# Scheme.net
KiCad netlist of a schematic drawn in Altium Designer
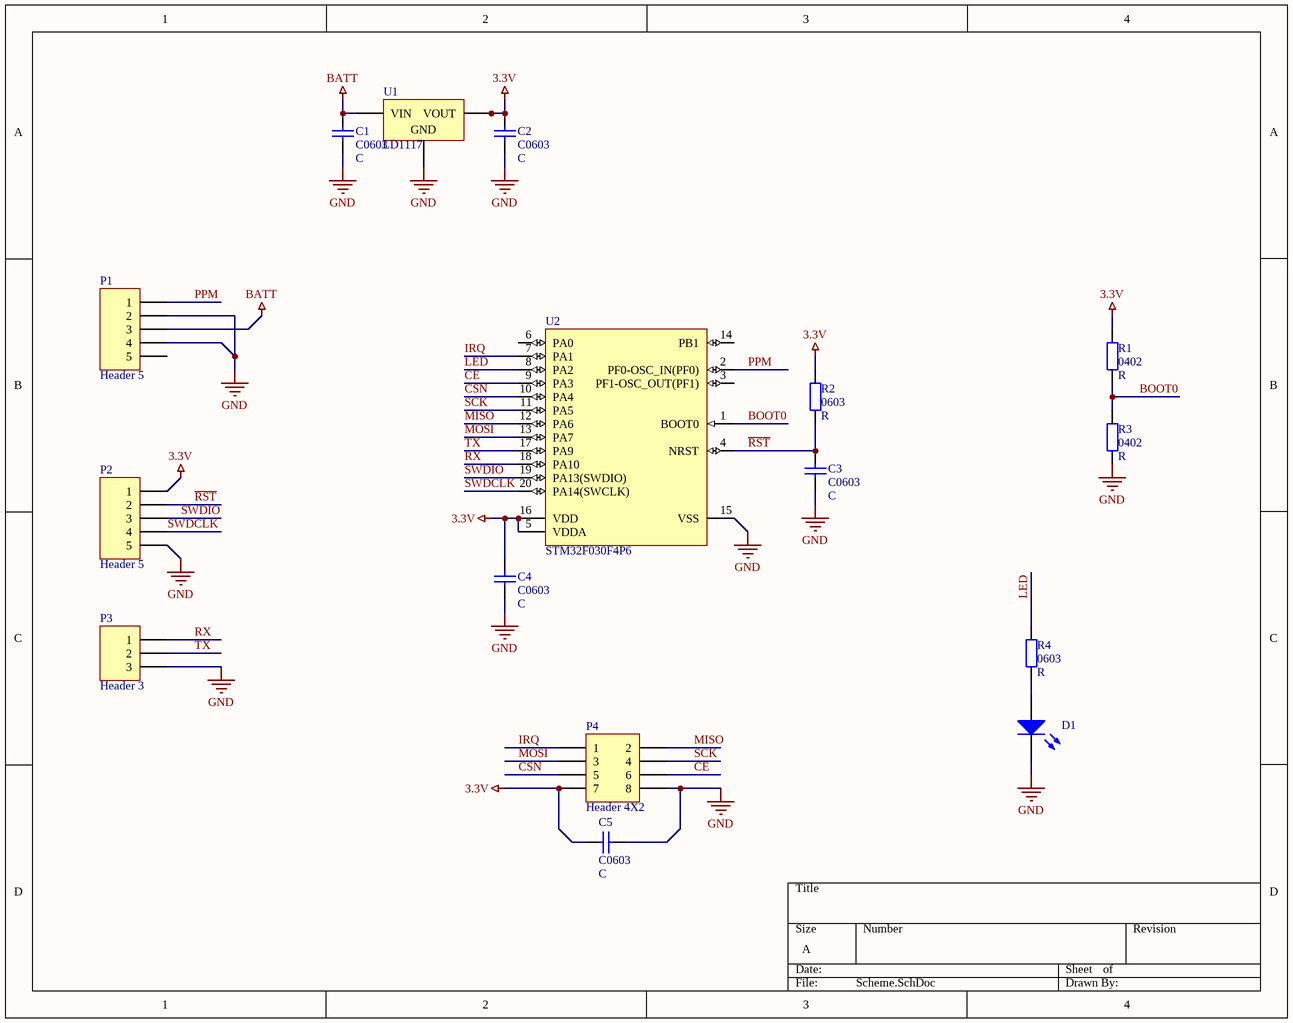
[diagram p0: Scheme.SchDoc]

(export (version "E")
  (design (tool "Eeschema 10.0.6"))
  (components
    (comp (ref "C1")
      (value "C")
      (footprint "C0603")
      (description "Generic capacitor")
      (libsource (lib "_RLC") (part "Cap"))
    )
    (comp (ref "C2")
      (value "C")
      (footprint "C0603")
      (description "Generic capacitor")
      (libsource (lib "_RLC") (part "Cap"))
    )
    (comp (ref "C3")
      (value "C")
      (footprint "C0603")
      (description "Generic capacitor")
      (libsource (lib "_RLC") (part "Cap"))
    )
    (comp (ref "C4")
      (value "C")
      (footprint "C0603")
      (description "Generic capacitor")
      (libsource (lib "_RLC") (part "Cap"))
    )
    (comp (ref "C5")
      (value "C")
      (footprint "C0603")
      (description "Generic capacitor")
      (libsource (lib "_RLC") (part "Cap"))
    )
    (comp (ref "D1")
      (value "LEDX")
      (footprint "LED 0805 RED")
      (description "Typical LED")
      (libsource (lib "_Diodes") (part "LEDX"))
    )
    (comp (ref "P1")
      (value "Header 5")
      (footprint "HEADER 1X5 FEMALE")
      (description "Header, 5-Pin")
      (fields (field (name "PUBLISHER") "Altium Limited"))
      (libsource (lib "_Connectors") (part "Header 5"))
    )
    (comp (ref "P2")
      (value "Header 5")
      (footprint "HEADER 1X5 FEMALE")
      (description "Header, 5-Pin")
      (fields (field (name "PUBLISHER") "Altium Limited"))
      (libsource (lib "_Connectors") (part "Header 5"))
    )
    (comp (ref "P3")
      (value "Header 3")
      (footprint "HEADER 1X3 MALE")
      (description "Header, 3-Pin")
      (fields (field (name "PUBLISHER") "Altium Limited"))
      (libsource (lib "_Connectors") (part "Header 3"))
    )
    (comp (ref "P4")
      (value "Header 4X2")
      (footprint "HEADER 2X4 FEMALE")
      (description "Header, 4-Pin, Dual row")
      (fields (field (name "PUBLISHER") "Altium Limited"))
      (libsource (lib "_Connectors") (part "Header 4X2"))
    )
    (comp (ref "R1")
      (value "R")
      (footprint "0402")
      (description "Generic resistor")
      (libsource (lib "_RLC") (part "Res"))
    )
    (comp (ref "R2")
      (value "R")
      (footprint "0603")
      (description "Generic resistor")
      (libsource (lib "_RLC") (part "Res"))
    )
    (comp (ref "R3")
      (value "R")
      (footprint "0402")
      (description "Generic resistor")
      (libsource (lib "_RLC") (part "Res"))
    )
    (comp (ref "R4")
      (value "R")
      (footprint "0603")
      (description "Generic resistor")
      (libsource (lib "_RLC") (part "Res"))
    )
    (comp (ref "U1")
      (value "LD1117")
      (footprint "TO-252")
      (description "Low drop positive voltage regulator")
      (libsource (lib "_Microcircuits") (part "LD1117"))
    )
    (comp (ref "U2")
      (value "STM32F030F4P6")
      (footprint "SSOP20_M")
      (libsource (lib "_Microcircuits") (part "STM32F030F4P6"))
    )
  )
  (nets
    (net (code "1") (name "/BOOT0") (class "Default")
      (node (ref "R1") (pin "2") (pinfunction "2_2") (pintype "passive"))
      (node (ref "R3") (pin "1") (pinfunction "1_1") (pintype "passive"))
      (node (ref "U2") (pin "1") (pinfunction "BOOT0_1") (pintype "input"))
    )
    (net (code "2") (name "/CE") (class "Default")
      (node (ref "P4") (pin "6") (pinfunction "6_6") (pintype "passive"))
      (node (ref "U2") (pin "9") (pinfunction "PA3_9") (pintype "bidirectional"))
    )
    (net (code "3") (name "/CSN") (class "Default")
      (node (ref "P4") (pin "5") (pinfunction "5_5") (pintype "passive"))
      (node (ref "U2") (pin "10") (pinfunction "PA4_10") (pintype "bidirectional"))
    )
    (net (code "4") (name "/IRQ") (class "Default")
      (node (ref "P4") (pin "1") (pinfunction "1_1") (pintype "passive"))
      (node (ref "U2") (pin "7") (pinfunction "PA1_7") (pintype "bidirectional"))
    )
    (net (code "5") (name "/LED") (class "Default")
      (node (ref "R4") (pin "1") (pinfunction "1_1") (pintype "passive"))
      (node (ref "U2") (pin "8") (pinfunction "PA2_8") (pintype "bidirectional"))
    )
    (net (code "6") (name "/MISO") (class "Default")
      (node (ref "P4") (pin "2") (pinfunction "2_2") (pintype "passive"))
      (node (ref "U2") (pin "12") (pinfunction "PA6_12") (pintype "bidirectional"))
    )
    (net (code "7") (name "/MOSI") (class "Default")
      (node (ref "P4") (pin "3") (pinfunction "3_3") (pintype "passive"))
      (node (ref "U2") (pin "13") (pinfunction "PA7_13") (pintype "bidirectional"))
    )
    (net (code "8") (name "/PPM") (class "Default")
      (node (ref "P1") (pin "1") (pinfunction "1_1") (pintype "passive"))
      (node (ref "U2") (pin "2") (pinfunction "PF0-OSC_IN(PF0)_2") (pintype "bidirectional"))
    )
    (net (code "9") (name "/RST") (class "Default")
      (node (ref "C3") (pin "1") (pinfunction "1_1") (pintype "passive"))
      (node (ref "P2") (pin "2") (pinfunction "2_2") (pintype "passive"))
      (node (ref "R2") (pin "2") (pinfunction "2_2") (pintype "passive"))
      (node (ref "U2") (pin "4") (pinfunction "NRST_4") (pintype "bidirectional"))
    )
    (net (code "10") (name "/RX") (class "Default")
      (node (ref "P3") (pin "1") (pinfunction "1_1") (pintype "passive"))
      (node (ref "U2") (pin "18") (pinfunction "PA10_18") (pintype "bidirectional"))
    )
    (net (code "11") (name "/SCK") (class "Default")
      (node (ref "P4") (pin "4") (pinfunction "4_4") (pintype "passive"))
      (node (ref "U2") (pin "11") (pinfunction "PA5_11") (pintype "bidirectional"))
    )
    (net (code "12") (name "/SWDCLK") (class "Default")
      (node (ref "P2") (pin "4") (pinfunction "4_4") (pintype "passive"))
      (node (ref "U2") (pin "20") (pinfunction "PA14(SWCLK)_20") (pintype "bidirectional"))
    )
    (net (code "13") (name "/SWDIO") (class "Default")
      (node (ref "P2") (pin "3") (pinfunction "3_3") (pintype "passive"))
      (node (ref "U2") (pin "19") (pinfunction "PA13(SWDIO)_19") (pintype "bidirectional"))
    )
    (net (code "14") (name "/TX") (class "Default")
      (node (ref "P3") (pin "2") (pinfunction "2_2") (pintype "passive"))
      (node (ref "U2") (pin "17") (pinfunction "PA9_17") (pintype "bidirectional"))
    )
    (net (code "15") (name "3.3V") (class "Default")
      (node (ref "C2") (pin "2") (pinfunction "2_2") (pintype "passive"))
      (node (ref "C4") (pin "1") (pinfunction "1_1") (pintype "passive"))
      (node (ref "C5") (pin "1") (pinfunction "1_1") (pintype "passive"))
      (node (ref "P2") (pin "1") (pinfunction "1_1") (pintype "passive"))
      (node (ref "P4") (pin "7") (pinfunction "7_7") (pintype "passive"))
      (node (ref "R1") (pin "1") (pinfunction "1_1") (pintype "passive"))
      (node (ref "R2") (pin "1") (pinfunction "1_1") (pintype "passive"))
      (node (ref "U1") (pin "2") (pinfunction "VOUT_2") (pintype "power_in"))
      (node (ref "U1") (pin "4") (pinfunction "VOUT_4") (pintype "power_in"))
      (node (ref "U1") (pin "5") (pinfunction "VOUT_5") (pintype "power_in"))
      (node (ref "U1") (pin "6") (pinfunction "VOUT_6") (pintype "power_in"))
      (node (ref "U2") (pin "16") (pinfunction "VDD_16") (pintype "power_in"))
      (node (ref "U2") (pin "5") (pinfunction "VDDA_5") (pintype "power_in"))
    )
    (net (code "16") (name "BATT") (class "Default")
      (node (ref "C1") (pin "2") (pinfunction "2_2") (pintype "passive"))
      (node (ref "P1") (pin "3") (pinfunction "3_3") (pintype "passive"))
      (node (ref "U1") (pin "3") (pinfunction "VIN_3") (pintype "power_in"))
    )
    (net (code "17") (name "GND") (class "Default")
      (node (ref "C1") (pin "1") (pinfunction "1_1") (pintype "passive"))
      (node (ref "C2") (pin "1") (pinfunction "1_1") (pintype "passive"))
      (node (ref "C3") (pin "2") (pinfunction "2_2") (pintype "passive"))
      (node (ref "C4") (pin "2") (pinfunction "2_2") (pintype "passive"))
      (node (ref "C5") (pin "2") (pinfunction "2_2") (pintype "passive"))
      (node (ref "D1") (pin "2") (pinfunction "K_2") (pintype "passive"))
      (node (ref "P1") (pin "2") (pinfunction "2_2") (pintype "passive"))
      (node (ref "P1") (pin "4") (pinfunction "4_4") (pintype "passive"))
      (node (ref "P2") (pin "5") (pinfunction "5_5") (pintype "passive"))
      (node (ref "P3") (pin "3") (pinfunction "3_3") (pintype "passive"))
      (node (ref "P4") (pin "8") (pinfunction "8_8") (pintype "passive"))
      (node (ref "R3") (pin "2") (pinfunction "2_2") (pintype "passive"))
      (node (ref "U1") (pin "1") (pinfunction "GND_1") (pintype "power_in"))
      (node (ref "U2") (pin "15") (pinfunction "VSS_15") (pintype "power_in"))
    )
    (net (code "18") (name "Net-(D1-A)") (class "Default")
      (node (ref "D1") (pin "1") (pinfunction "A_1") (pintype "passive"))
      (node (ref "R4") (pin "2") (pinfunction "2_2") (pintype "passive"))
    )
    (net (code "19") (name "unconnected-(P1-Pad5)") (class "Default")
      (node (ref "P1") (pin "5") (pinfunction "5_5") (pintype "passive"))
    )
    (net (code "20") (name "unconnected-(U2-PA0-Pad6)") (class "Default")
      (node (ref "U2") (pin "6") (pinfunction "PA0_6") (pintype "bidirectional"))
    )
    (net (code "21") (name "unconnected-(U2-PB1-Pad14)") (class "Default")
      (node (ref "U2") (pin "14") (pinfunction "PB1_14") (pintype "bidirectional"))
    )
    (net (code "22") (name "unconnected-(U2-PF1-OSC_OUT(PF1)-Pad3)") (class "Default")
      (node (ref "U2") (pin "3") (pinfunction "PF1-OSC_OUT(PF1)_3") (pintype "bidirectional"))
    )
  )
)
